# RTC_and_EEPROM.net
KiCad netlist of a schematic drawn in Altium Designer
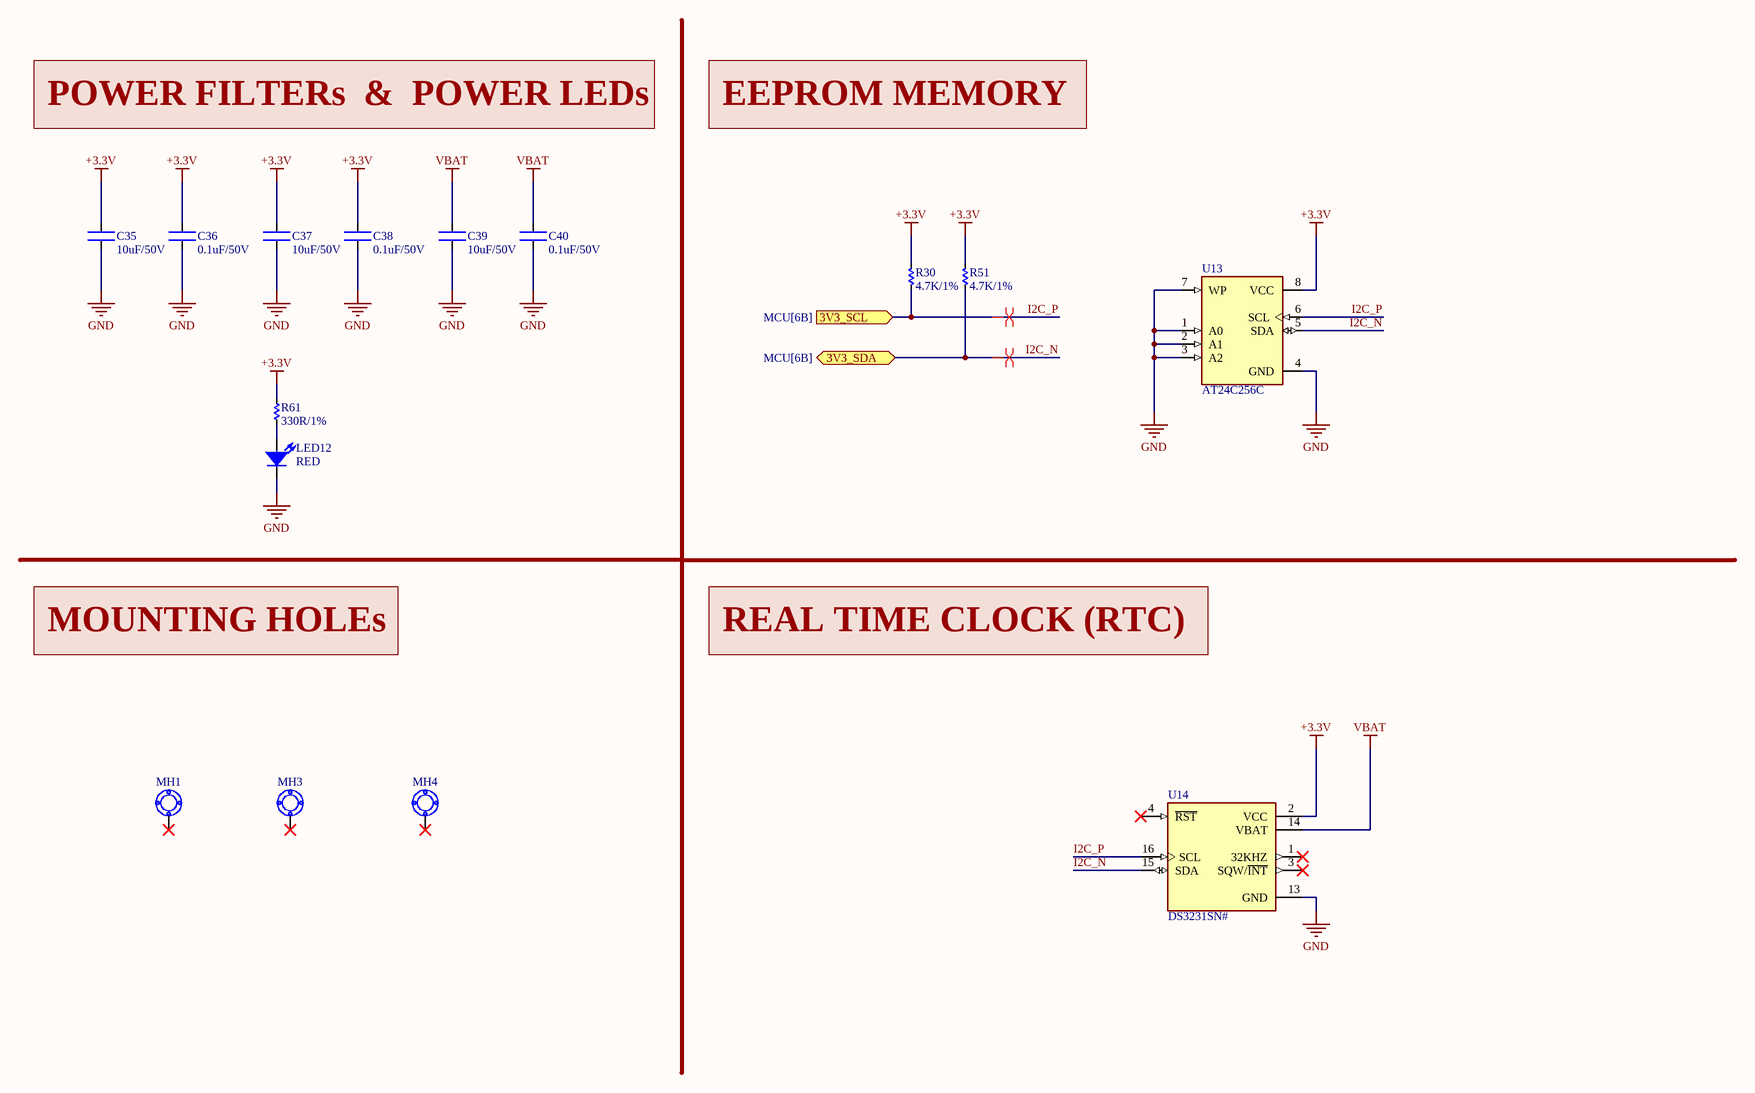
[diagram p0: RTC_and_EEPROM.SchDoc]

(export (version "E")
  (design (tool "Eeschema 10.0.6"))
  (components
    (comp (ref "C35")
      (value "10uF/50V")
      (footprint "CAP - 0603")
      (description "CAPACITOR SMD - KEMET")
      (libsource (lib "NewLibrary") (part "CAPACITOR"))
    )
    (comp (ref "C36")
      (value "0.1uF/50V")
      (footprint "CAP - 0603")
      (description "CAPACITOR SMD - KEMET")
      (libsource (lib "NewLibrary") (part "CAPACITOR"))
    )
    (comp (ref "C37")
      (value "10uF/50V")
      (footprint "CAP - 0603")
      (description "CAPACITOR SMD - KEMET")
      (libsource (lib "NewLibrary") (part "CAPACITOR"))
    )
    (comp (ref "C38")
      (value "0.1uF/50V")
      (footprint "CAP - 0603")
      (description "CAPACITOR SMD - KEMET")
      (libsource (lib "NewLibrary") (part "CAPACITOR"))
    )
    (comp (ref "C39")
      (value "10uF/50V")
      (footprint "CAP - 0603")
      (description "CAPACITOR SMD - KEMET")
      (libsource (lib "NewLibrary") (part "CAPACITOR"))
    )
    (comp (ref "C40")
      (value "0.1uF/50V")
      (footprint "CAP - 0603")
      (description "CAPACITOR SMD - KEMET")
      (libsource (lib "NewLibrary") (part "CAPACITOR"))
    )
    (comp (ref "LED12")
      (value "RED")
      (footprint "RED_LED_0603")
      (description "LED SMD")
      (libsource (lib "NewLibrary") (part "LED_SMD"))
    )
    (comp (ref "MH1")
      (value "MOUNTING HOLE")
      (footprint "Mounting hole_2")
      (description "Mounting hole")
      (libsource (lib "NewLibrary") (part "MOUNTING HOLE"))
    )
    (comp (ref "MH3")
      (value "MOUNTING HOLE")
      (footprint "Mounting hole_2")
      (description "Mounting hole")
      (libsource (lib "NewLibrary") (part "MOUNTING HOLE"))
    )
    (comp (ref "MH4")
      (value "MOUNTING HOLE")
      (footprint "Mounting hole_2")
      (description "Mounting hole")
      (libsource (lib "NewLibrary") (part "MOUNTING HOLE"))
    )
    (comp (ref "R30")
      (value "4.7K/1%")
      (footprint "RES - 0603")
      (description "Resistor SMD - YAGEO")
      (libsource (lib "NewLibrary") (part "RESISTOR"))
    )
    (comp (ref "R51")
      (value "4.7K/1%")
      (footprint "RES - 0603")
      (description "Resistor SMD - YAGEO")
      (libsource (lib "NewLibrary") (part "RESISTOR"))
    )
    (comp (ref "R61")
      (value "330R/1%")
      (footprint "RES - 0603")
      (description "Resistor SMD - YAGEO")
      (libsource (lib "NewLibrary") (part "RESISTOR"))
    )
    (comp (ref "U13")
      (value "AT24C256C")
      (footprint "SOIC-8")
      (description "EEPROM Memory IC 256Kb (32K x 8), I2C Protocol")
      (libsource (lib "NewLibrary") (part "AT24C256C"))
    )
    (comp (ref "U14")
      (value "DS3231SN#")
      (footprint "SOIC -16")
      (description "Extremely Accurate I²C-Integrated RTC/TCXO/Crystal")
      (libsource (lib "NewLibrary") (part "DS3231SN#"))
    )
  )
  (nets
    (net (code "1") (name "+3.3V") (class "Default")
      (node (ref "C35") (pin "2") (pinfunction "2_2") (pintype "passive"))
      (node (ref "C36") (pin "2") (pinfunction "2_2") (pintype "passive"))
      (node (ref "C37") (pin "2") (pinfunction "2_2") (pintype "passive"))
      (node (ref "C38") (pin "2") (pinfunction "2_2") (pintype "passive"))
      (node (ref "R30") (pin "2") (pinfunction "2_2") (pintype "passive"))
      (node (ref "R51") (pin "2") (pinfunction "2_2") (pintype "passive"))
      (node (ref "R61") (pin "1") (pinfunction "1_1") (pintype "passive"))
      (node (ref "U13") (pin "8") (pinfunction "VCC_8") (pintype "power_in"))
      (node (ref "U14") (pin "2") (pinfunction "VCC_2") (pintype "power_in"))
    )
    (net (code "2") (name "/I2C_N") (class "Default")
      (node (ref "R51") (pin "1") (pinfunction "1_1") (pintype "passive"))
      (node (ref "U13") (pin "5") (pinfunction "SDA_5") (pintype "bidirectional"))
      (node (ref "U14") (pin "15") (pinfunction "SDA_15") (pintype "bidirectional"))
    )
    (net (code "3") (name "/I2C_P") (class "Default")
      (node (ref "R30") (pin "1") (pinfunction "1_1") (pintype "passive"))
      (node (ref "U13") (pin "6") (pinfunction "SCL_6") (pintype "input"))
      (node (ref "U14") (pin "16") (pinfunction "SCL_16") (pintype "input"))
    )
    (net (code "4") (name "GND") (class "Default")
      (node (ref "C35") (pin "1") (pinfunction "1_1") (pintype "passive"))
      (node (ref "C36") (pin "1") (pinfunction "1_1") (pintype "passive"))
      (node (ref "C37") (pin "1") (pinfunction "1_1") (pintype "passive"))
      (node (ref "C38") (pin "1") (pinfunction "1_1") (pintype "passive"))
      (node (ref "C39") (pin "1") (pinfunction "1_1") (pintype "passive"))
      (node (ref "C40") (pin "1") (pinfunction "1_1") (pintype "passive"))
      (node (ref "LED12") (pin "2") (pinfunction "2_2") (pintype "passive"))
      (node (ref "U13") (pin "1") (pinfunction "A0_1") (pintype "input"))
      (node (ref "U13") (pin "2") (pinfunction "A1_2") (pintype "input"))
      (node (ref "U13") (pin "3") (pinfunction "A2_3") (pintype "input"))
      (node (ref "U13") (pin "4") (pinfunction "GND_4") (pintype "power_in"))
      (node (ref "U13") (pin "7") (pinfunction "WP_7") (pintype "input"))
      (node (ref "U14") (pin "13") (pinfunction "GND_13") (pintype "power_in"))
    )
    (net (code "5") (name "Net-(LED12-Pad1)") (class "Default")
      (node (ref "LED12") (pin "1") (pinfunction "1_1") (pintype "passive"))
      (node (ref "R61") (pin "2") (pinfunction "2_2") (pintype "passive"))
    )
    (net (code "6") (name "VBAT") (class "Default")
      (node (ref "C39") (pin "2") (pinfunction "2_2") (pintype "passive"))
      (node (ref "C40") (pin "2") (pinfunction "2_2") (pintype "passive"))
      (node (ref "U14") (pin "14") (pinfunction "VBAT_14") (pintype "power_in"))
    )
    (net (code "7") (name "unconnected-(MH1-76-Pad1)") (class "Default")
      (node (ref "MH1") (pin "1") (pinfunction "76_1") (pintype "passive+no_connect"))
    )
    (net (code "8") (name "unconnected-(MH3-76-Pad1)") (class "Default")
      (node (ref "MH3") (pin "1") (pinfunction "76_1") (pintype "passive+no_connect"))
    )
    (net (code "9") (name "unconnected-(MH4-76-Pad1)") (class "Default")
      (node (ref "MH4") (pin "1") (pinfunction "76_1") (pintype "passive+no_connect"))
    )
    (net (code "10") (name "unconnected-(U14-32KHZ-Pad1)") (class "Default")
      (node (ref "U14") (pin "1") (pinfunction "32KHZ_1") (pintype "output+no_connect"))
    )
    (net (code "11") (name "unconnected-(U14-SQW{slash}~{INT}-Pad3)") (class "Default")
      (node (ref "U14") (pin "3") (pinfunction "SQW/~{INT}_3") (pintype "output+no_connect"))
    )
    (net (code "12") (name "unconnected-(U14-~{RST}-Pad4)") (class "Default")
      (node (ref "U14") (pin "4") (pinfunction "~{RST}_4") (pintype "input+no_connect"))
    )
  )
)
